# Wordclock-back-smd.net
KiCad netlist of a schematic drawn in EAGLE
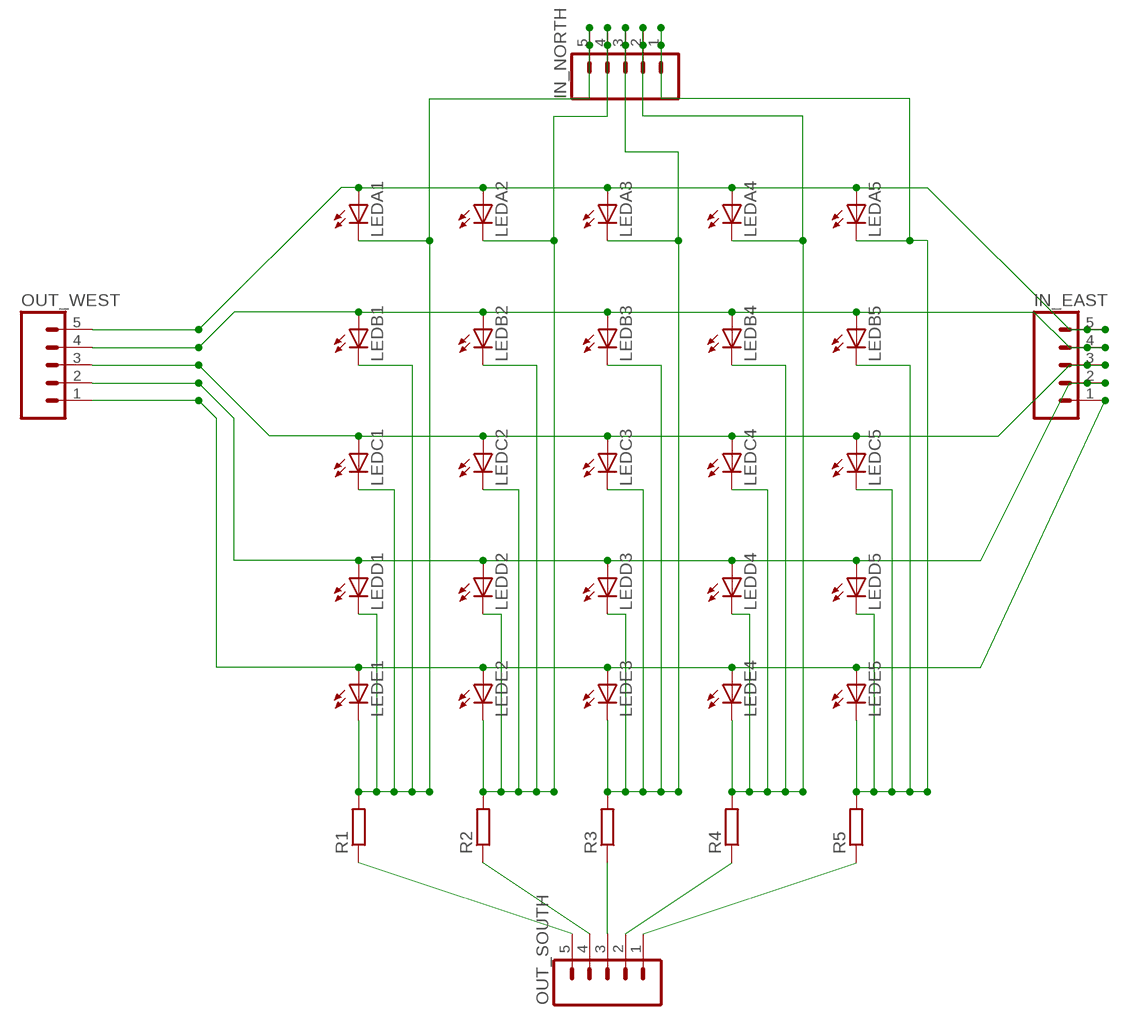
[diagram p0: schematic, sheet 1]

(export (version "E")
  (design (tool "Eeschema 10.0.6"))
  (components
    (comp (ref "IN_EAST")
      (value "M05PTH")
      (footprint "eagle-import:1X05")
      (libsource (lib "eagle-import") (part "M05PTH"))
    )
    (comp (ref "IN_NORTH")
      (value "M05PTH")
      (footprint "eagle-import:1X05")
      (libsource (lib "eagle-import") (part "M05PTH"))
    )
    (comp (ref "LEDA1")
      (value "LEDKA-3528ASYC")
      (footprint "eagle-import:KA-3528ASYC")
      (libsource (lib "eagle-import") (part "LEDKA-3528ASYC"))
    )
    (comp (ref "LEDA2")
      (value "LEDKA-3528ASYC")
      (footprint "eagle-import:KA-3528ASYC")
      (libsource (lib "eagle-import") (part "LEDKA-3528ASYC"))
    )
    (comp (ref "LEDA3")
      (value "LEDKA-3528ASYC")
      (footprint "eagle-import:KA-3528ASYC")
      (libsource (lib "eagle-import") (part "LEDKA-3528ASYC"))
    )
    (comp (ref "LEDA4")
      (value "LEDKA-3528ASYC")
      (footprint "eagle-import:KA-3528ASYC")
      (libsource (lib "eagle-import") (part "LEDKA-3528ASYC"))
    )
    (comp (ref "LEDA5")
      (value "LEDKA-3528ASYC")
      (footprint "eagle-import:KA-3528ASYC")
      (libsource (lib "eagle-import") (part "LEDKA-3528ASYC"))
    )
    (comp (ref "LEDB1")
      (value "LEDKA-3528ASYC")
      (footprint "eagle-import:KA-3528ASYC")
      (libsource (lib "eagle-import") (part "LEDKA-3528ASYC"))
    )
    (comp (ref "LEDB2")
      (value "LEDKA-3528ASYC")
      (footprint "eagle-import:KA-3528ASYC")
      (libsource (lib "eagle-import") (part "LEDKA-3528ASYC"))
    )
    (comp (ref "LEDB3")
      (value "LEDKA-3528ASYC")
      (footprint "eagle-import:KA-3528ASYC")
      (libsource (lib "eagle-import") (part "LEDKA-3528ASYC"))
    )
    (comp (ref "LEDB4")
      (value "LEDKA-3528ASYC")
      (footprint "eagle-import:KA-3528ASYC")
      (libsource (lib "eagle-import") (part "LEDKA-3528ASYC"))
    )
    (comp (ref "LEDB5")
      (value "LEDKA-3528ASYC")
      (footprint "eagle-import:KA-3528ASYC")
      (libsource (lib "eagle-import") (part "LEDKA-3528ASYC"))
    )
    (comp (ref "LEDC1")
      (value "LEDKA-3528ASYC")
      (footprint "eagle-import:KA-3528ASYC")
      (libsource (lib "eagle-import") (part "LEDKA-3528ASYC"))
    )
    (comp (ref "LEDC2")
      (value "LEDKA-3528ASYC")
      (footprint "eagle-import:KA-3528ASYC")
      (libsource (lib "eagle-import") (part "LEDKA-3528ASYC"))
    )
    (comp (ref "LEDC3")
      (value "LEDKA-3528ASYC")
      (footprint "eagle-import:KA-3528ASYC")
      (libsource (lib "eagle-import") (part "LEDKA-3528ASYC"))
    )
    (comp (ref "LEDC4")
      (value "LEDKA-3528ASYC")
      (footprint "eagle-import:KA-3528ASYC")
      (libsource (lib "eagle-import") (part "LEDKA-3528ASYC"))
    )
    (comp (ref "LEDC5")
      (value "LEDKA-3528ASYC")
      (footprint "eagle-import:KA-3528ASYC")
      (libsource (lib "eagle-import") (part "LEDKA-3528ASYC"))
    )
    (comp (ref "LEDD1")
      (value "LEDKA-3528ASYC")
      (footprint "eagle-import:KA-3528ASYC")
      (libsource (lib "eagle-import") (part "LEDKA-3528ASYC"))
    )
    (comp (ref "LEDD2")
      (value "LEDKA-3528ASYC")
      (footprint "eagle-import:KA-3528ASYC")
      (libsource (lib "eagle-import") (part "LEDKA-3528ASYC"))
    )
    (comp (ref "LEDD3")
      (value "LEDKA-3528ASYC")
      (footprint "eagle-import:KA-3528ASYC")
      (libsource (lib "eagle-import") (part "LEDKA-3528ASYC"))
    )
    (comp (ref "LEDD4")
      (value "LEDKA-3528ASYC")
      (footprint "eagle-import:KA-3528ASYC")
      (libsource (lib "eagle-import") (part "LEDKA-3528ASYC"))
    )
    (comp (ref "LEDD5")
      (value "LEDKA-3528ASYC")
      (footprint "eagle-import:KA-3528ASYC")
      (libsource (lib "eagle-import") (part "LEDKA-3528ASYC"))
    )
    (comp (ref "LEDE1")
      (value "LEDKA-3528ASYC")
      (footprint "eagle-import:KA-3528ASYC")
      (libsource (lib "eagle-import") (part "LEDKA-3528ASYC"))
    )
    (comp (ref "LEDE2")
      (value "LEDKA-3528ASYC")
      (footprint "eagle-import:KA-3528ASYC")
      (libsource (lib "eagle-import") (part "LEDKA-3528ASYC"))
    )
    (comp (ref "LEDE3")
      (value "LEDKA-3528ASYC")
      (footprint "eagle-import:KA-3528ASYC")
      (libsource (lib "eagle-import") (part "LEDKA-3528ASYC"))
    )
    (comp (ref "LEDE4")
      (value "LEDKA-3528ASYC")
      (footprint "eagle-import:KA-3528ASYC")
      (libsource (lib "eagle-import") (part "LEDKA-3528ASYC"))
    )
    (comp (ref "LEDE5")
      (value "LEDKA-3528ASYC")
      (footprint "eagle-import:KA-3528ASYC")
      (libsource (lib "eagle-import") (part "LEDKA-3528ASYC"))
    )
    (comp (ref "OUT_SOUTH")
      (value "M05PTH")
      (footprint "eagle-import:1X05")
      (libsource (lib "eagle-import") (part "M05PTH"))
    )
    (comp (ref "OUT_WEST")
      (value "M05PTH")
      (footprint "eagle-import:1X05")
      (libsource (lib "eagle-import") (part "M05PTH"))
    )
    (comp (ref "R1")
      (value "R-EU_0207/10")
      (footprint "eagle-import:0207_10")
      (libsource (lib "eagle-import") (part "R-EU_0207/10"))
    )
    (comp (ref "R2")
      (value "R-EU_0207/10")
      (footprint "eagle-import:0207_10")
      (libsource (lib "eagle-import") (part "R-EU_0207/10"))
    )
    (comp (ref "R3")
      (value "R-EU_0207/10")
      (footprint "eagle-import:0207_10")
      (libsource (lib "eagle-import") (part "R-EU_0207/10"))
    )
    (comp (ref "R4")
      (value "R-EU_0207/10")
      (footprint "eagle-import:0207_10")
      (libsource (lib "eagle-import") (part "R-EU_0207/10"))
    )
    (comp (ref "R5")
      (value "R-EU_0207/10")
      (footprint "eagle-import:0207_10")
      (libsource (lib "eagle-import") (part "R-EU_0207/10"))
    )
  )
  (nets
    (net (code "1") (name "Net-(IN_EAST-Pad1)") (class "Default")
      (node (ref "IN_EAST") (pin "1") (pinfunction "1_1") (pintype "passive"))
      (node (ref "LEDE1") (pin "A") (pinfunction "A_A") (pintype "passive"))
      (node (ref "LEDE2") (pin "A") (pinfunction "A_A") (pintype "passive"))
      (node (ref "LEDE3") (pin "A") (pinfunction "A_A") (pintype "passive"))
      (node (ref "LEDE4") (pin "A") (pinfunction "A_A") (pintype "passive"))
      (node (ref "LEDE5") (pin "A") (pinfunction "A_A") (pintype "passive"))
      (node (ref "OUT_WEST") (pin "1") (pinfunction "1_1") (pintype "passive"))
    )
    (net (code "2") (name "Net-(IN_EAST-Pad2)") (class "Default")
      (node (ref "IN_EAST") (pin "2") (pinfunction "2_2") (pintype "passive"))
      (node (ref "LEDD1") (pin "A") (pinfunction "A_A") (pintype "passive"))
      (node (ref "LEDD2") (pin "A") (pinfunction "A_A") (pintype "passive"))
      (node (ref "LEDD3") (pin "A") (pinfunction "A_A") (pintype "passive"))
      (node (ref "LEDD4") (pin "A") (pinfunction "A_A") (pintype "passive"))
      (node (ref "LEDD5") (pin "A") (pinfunction "A_A") (pintype "passive"))
      (node (ref "OUT_WEST") (pin "2") (pinfunction "2_2") (pintype "passive"))
    )
    (net (code "3") (name "Net-(IN_EAST-Pad3)") (class "Default")
      (node (ref "IN_EAST") (pin "3") (pinfunction "3_3") (pintype "passive"))
      (node (ref "LEDC1") (pin "A") (pinfunction "A_A") (pintype "passive"))
      (node (ref "LEDC2") (pin "A") (pinfunction "A_A") (pintype "passive"))
      (node (ref "LEDC3") (pin "A") (pinfunction "A_A") (pintype "passive"))
      (node (ref "LEDC4") (pin "A") (pinfunction "A_A") (pintype "passive"))
      (node (ref "LEDC5") (pin "A") (pinfunction "A_A") (pintype "passive"))
      (node (ref "OUT_WEST") (pin "3") (pinfunction "3_3") (pintype "passive"))
    )
    (net (code "4") (name "Net-(IN_EAST-Pad4)") (class "Default")
      (node (ref "IN_EAST") (pin "4") (pinfunction "4_4") (pintype "passive"))
      (node (ref "LEDB1") (pin "A") (pinfunction "A_A") (pintype "passive"))
      (node (ref "LEDB2") (pin "A") (pinfunction "A_A") (pintype "passive"))
      (node (ref "LEDB3") (pin "A") (pinfunction "A_A") (pintype "passive"))
      (node (ref "LEDB4") (pin "A") (pinfunction "A_A") (pintype "passive"))
      (node (ref "LEDB5") (pin "A") (pinfunction "A_A") (pintype "passive"))
      (node (ref "OUT_WEST") (pin "4") (pinfunction "4_4") (pintype "passive"))
    )
    (net (code "5") (name "Net-(IN_EAST-Pad5)") (class "Default")
      (node (ref "IN_EAST") (pin "5") (pinfunction "5_5") (pintype "passive"))
      (node (ref "LEDA1") (pin "A") (pinfunction "A_A") (pintype "passive"))
      (node (ref "LEDA2") (pin "A") (pinfunction "A_A") (pintype "passive"))
      (node (ref "LEDA3") (pin "A") (pinfunction "A_A") (pintype "passive"))
      (node (ref "LEDA4") (pin "A") (pinfunction "A_A") (pintype "passive"))
      (node (ref "LEDA5") (pin "A") (pinfunction "A_A") (pintype "passive"))
      (node (ref "OUT_WEST") (pin "5") (pinfunction "5_5") (pintype "passive"))
    )
    (net (code "6") (name "Net-(IN_NORTH-Pad1)") (class "Default")
      (node (ref "IN_NORTH") (pin "1") (pinfunction "1_1") (pintype "passive"))
      (node (ref "LEDA5") (pin "C") (pinfunction "C_C") (pintype "passive"))
      (node (ref "LEDB5") (pin "C") (pinfunction "C_C") (pintype "passive"))
      (node (ref "LEDC5") (pin "C") (pinfunction "C_C") (pintype "passive"))
      (node (ref "LEDD5") (pin "C") (pinfunction "C_C") (pintype "passive"))
      (node (ref "LEDE5") (pin "C") (pinfunction "C_C") (pintype "passive"))
      (node (ref "R5") (pin "2") (pinfunction "2_2") (pintype "passive"))
    )
    (net (code "7") (name "Net-(IN_NORTH-Pad2)") (class "Default")
      (node (ref "IN_NORTH") (pin "2") (pinfunction "2_2") (pintype "passive"))
      (node (ref "LEDA4") (pin "C") (pinfunction "C_C") (pintype "passive"))
      (node (ref "LEDB4") (pin "C") (pinfunction "C_C") (pintype "passive"))
      (node (ref "LEDC4") (pin "C") (pinfunction "C_C") (pintype "passive"))
      (node (ref "LEDD4") (pin "C") (pinfunction "C_C") (pintype "passive"))
      (node (ref "LEDE4") (pin "C") (pinfunction "C_C") (pintype "passive"))
      (node (ref "R4") (pin "2") (pinfunction "2_2") (pintype "passive"))
    )
    (net (code "8") (name "Net-(IN_NORTH-Pad3)") (class "Default")
      (node (ref "IN_NORTH") (pin "3") (pinfunction "3_3") (pintype "passive"))
      (node (ref "LEDA3") (pin "C") (pinfunction "C_C") (pintype "passive"))
      (node (ref "LEDB3") (pin "C") (pinfunction "C_C") (pintype "passive"))
      (node (ref "LEDC3") (pin "C") (pinfunction "C_C") (pintype "passive"))
      (node (ref "LEDD3") (pin "C") (pinfunction "C_C") (pintype "passive"))
      (node (ref "LEDE3") (pin "C") (pinfunction "C_C") (pintype "passive"))
      (node (ref "R3") (pin "2") (pinfunction "2_2") (pintype "passive"))
    )
    (net (code "9") (name "Net-(IN_NORTH-Pad4)") (class "Default")
      (node (ref "IN_NORTH") (pin "4") (pinfunction "4_4") (pintype "passive"))
      (node (ref "LEDA2") (pin "C") (pinfunction "C_C") (pintype "passive"))
      (node (ref "LEDB2") (pin "C") (pinfunction "C_C") (pintype "passive"))
      (node (ref "LEDC2") (pin "C") (pinfunction "C_C") (pintype "passive"))
      (node (ref "LEDD2") (pin "C") (pinfunction "C_C") (pintype "passive"))
      (node (ref "LEDE2") (pin "C") (pinfunction "C_C") (pintype "passive"))
      (node (ref "R2") (pin "2") (pinfunction "2_2") (pintype "passive"))
    )
    (net (code "10") (name "Net-(IN_NORTH-Pad5)") (class "Default")
      (node (ref "IN_NORTH") (pin "5") (pinfunction "5_5") (pintype "passive"))
      (node (ref "LEDA1") (pin "C") (pinfunction "C_C") (pintype "passive"))
      (node (ref "LEDB1") (pin "C") (pinfunction "C_C") (pintype "passive"))
      (node (ref "LEDC1") (pin "C") (pinfunction "C_C") (pintype "passive"))
      (node (ref "LEDD1") (pin "C") (pinfunction "C_C") (pintype "passive"))
      (node (ref "LEDE1") (pin "C") (pinfunction "C_C") (pintype "passive"))
      (node (ref "R1") (pin "2") (pinfunction "2_2") (pintype "passive"))
    )
    (net (code "11") (name "Net-(OUT_SOUTH-Pad1)") (class "Default")
      (node (ref "OUT_SOUTH") (pin "1") (pinfunction "1_1") (pintype "passive"))
      (node (ref "R5") (pin "1") (pinfunction "1_1") (pintype "passive"))
    )
    (net (code "12") (name "Net-(OUT_SOUTH-Pad2)") (class "Default")
      (node (ref "OUT_SOUTH") (pin "2") (pinfunction "2_2") (pintype "passive"))
      (node (ref "R4") (pin "1") (pinfunction "1_1") (pintype "passive"))
    )
    (net (code "13") (name "Net-(OUT_SOUTH-Pad3)") (class "Default")
      (node (ref "OUT_SOUTH") (pin "3") (pinfunction "3_3") (pintype "passive"))
      (node (ref "R3") (pin "1") (pinfunction "1_1") (pintype "passive"))
    )
    (net (code "14") (name "Net-(OUT_SOUTH-Pad4)") (class "Default")
      (node (ref "OUT_SOUTH") (pin "4") (pinfunction "4_4") (pintype "passive"))
      (node (ref "R2") (pin "1") (pinfunction "1_1") (pintype "passive"))
    )
    (net (code "15") (name "Net-(OUT_SOUTH-Pad5)") (class "Default")
      (node (ref "OUT_SOUTH") (pin "5") (pinfunction "5_5") (pintype "passive"))
      (node (ref "R1") (pin "1") (pinfunction "1_1") (pintype "passive"))
    )
  )
)
